# SCH_Ventilador_2025-02-20.net
KiCad netlist of a schematic drawn in EasyEDA
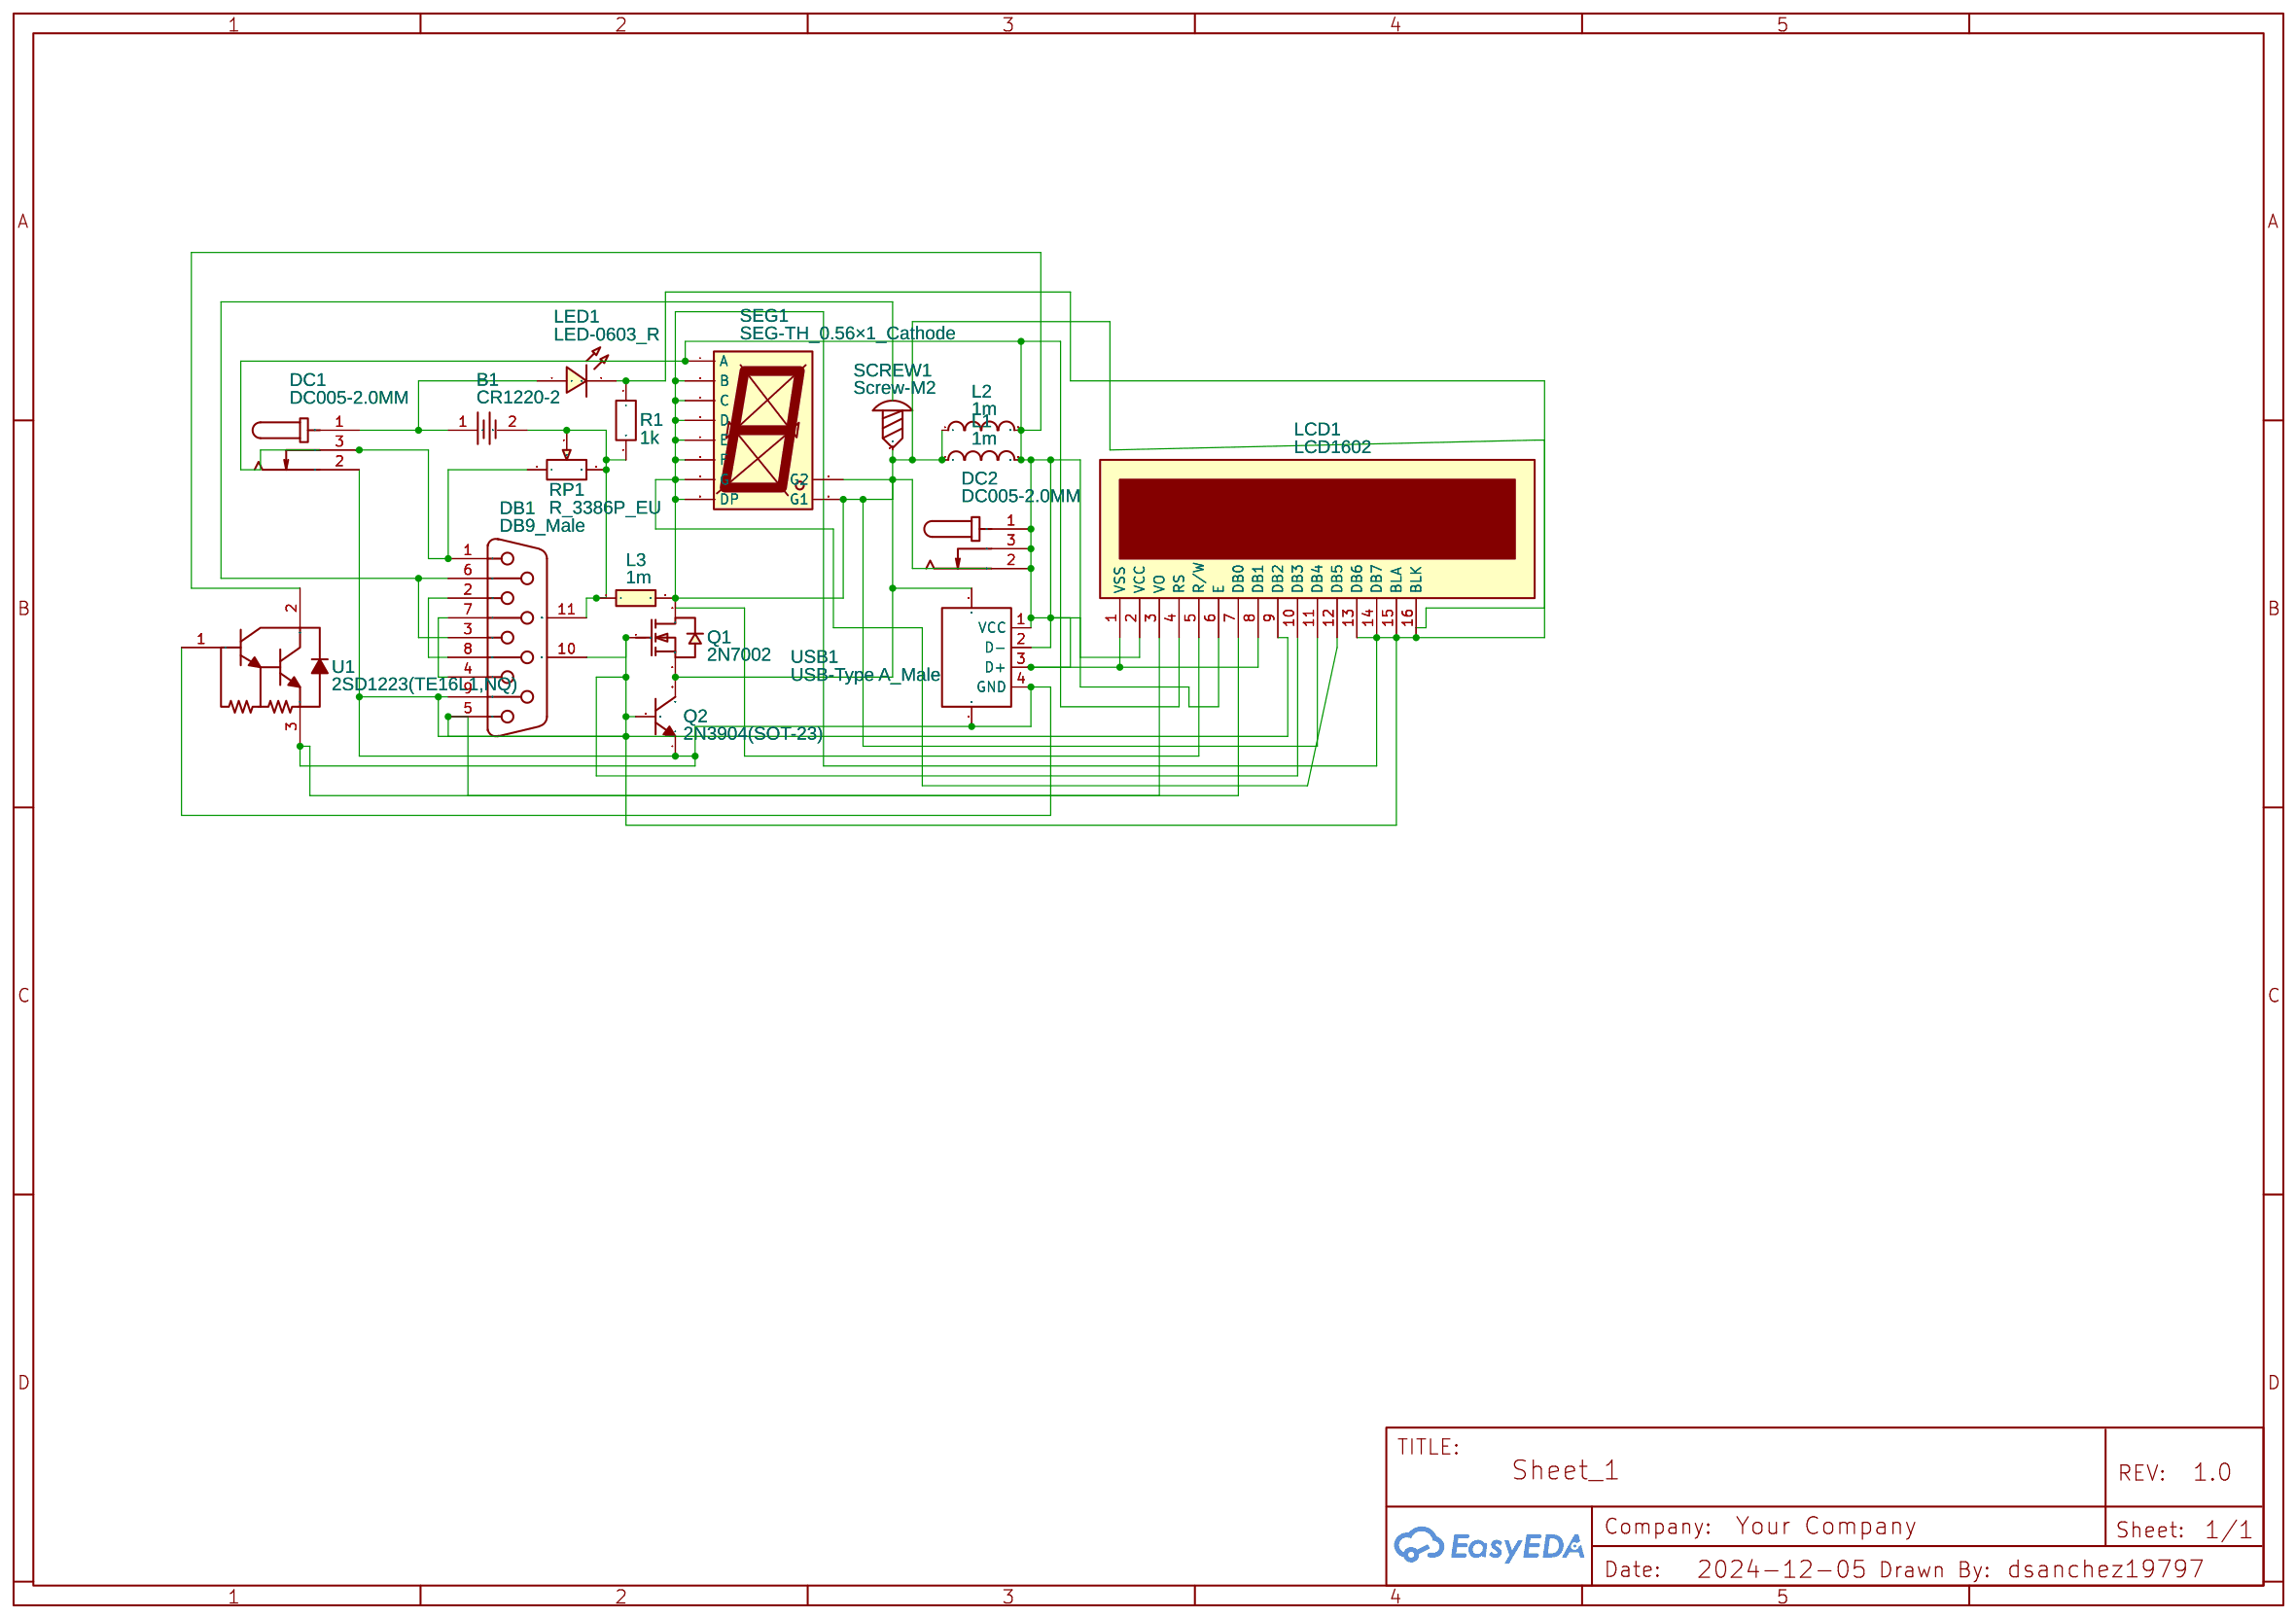
[diagram p0: schematic sheet]

(export (version "E")
  (design (tool "Eeschema 10.0.6"))
  (components
    (comp (ref "B1")
      (value "CR1220-2")
      (fields (field (name "Manufacturer") "Q&J"))
      (libsource (lib "") (part "CR1220-2"))
    )
    (comp (ref "DB1")
      (value "DB9_Male")
      (fields (field (name "Manufacturer") "Amphenol"))
      (libsource (lib "") (part "DB9_Male"))
    )
    (comp (ref "DC1")
      (value "DC005-2.0MM")
      (fields (field (name "Manufacturer") "SOFNG"))
      (libsource (lib "") (part "DC005-2.0MM"))
    )
    (comp (ref "DC2")
      (value "DC005-2.0MM")
      (fields (field (name "Manufacturer") "SOFNG"))
      (libsource (lib "") (part "DC005-2.0MM"))
    )
    (comp (ref "L1") (value "1m") (libsource (lib "") (part "L0603_US")))
    (comp (ref "L2") (value "1m") (libsource (lib "") (part "L0603_US")))
    (comp (ref "L3") (value "1m") (libsource (lib "") (part "L0603_EU")))
    (comp (ref "LCD1")
      (value "LCD1602")
      (fields
        (field (name "Manufacturer Part") "LCM1602K-NSW-BBW")
        (field (name "Manufacturer") "LONTECH(厦门龙特)")
      )
      (libsource (lib "") (part "LCD1602"))
    )
    (comp (ref "LED1")
      (value "LED-0603_R")
      (fields
        (field (name "Manufacturer Part") "19-217/R6C-AL1M2VY/3T")
        (field (name "Manufacturer") "EVERLIGHT(台湾亿光)")
      )
      (libsource (lib "") (part "LED-0603_R"))
    )
    (comp (ref "Q1")
      (value "2N7002")
      (fields (field (name "Manufacturer Part") "2N7002,215") (field (name "Manufacturer") "Nexperia"))
      (libsource (lib "") (part "2N7002"))
    )
    (comp (ref "Q2")
      (value "2N3904(SOT-23)")
      (fields (field (name "Manufacturer Part") "2n3904S-RTK/PS") (field (name "Manufacturer") "KEC"))
      (libsource (lib "") (part "2N3904(SOT-23)"))
    )
    (comp (ref "R1") (value "1k") (libsource (lib "") (part "R_0603_EU")))
    (comp (ref "RP1") (value "R_3386P_EU") (libsource (lib "") (part "R_3386P_EU")))
    (comp (ref "SCREW1") (value "Screw-M2") (libsource (lib "") (part "Screw-M2")))
    (comp (ref "SEG1")
      (value "SEG-TH_0.56×1_Cathode")
      (fields (field (name "Manufacturer") "志浩"))
      (libsource (lib "") (part "SEG-TH_0.56×1_Cathode"))
    )
    (comp (ref "U1")
      (value "2SD1223(TE16L1,NQ)")
      (fields (field (name "Manufacturer") "TOSHIBA(东芝)"))
      (libsource (lib "") (part "2SD1223(TE16L1,NQ)"))
    )
    (comp (ref "USB1")
      (value "USB-Type A_Male")
      (fields (field (name "Manufacturer Part") "USB-05") (field (name "Manufacturer") "SOFNG"))
      (libsource (lib "") (part "USB-Type A_Male"))
    )
  )
  (nets
    (net (code "1") (name "Net-(B1-Pad1)") (class "Default")
      (node (ref "B1") (pin "1") (pinfunction "1_1") (pintype "input"))
      (node (ref "DC1") (pin "1") (pinfunction "1_1") (pintype "unspecified"))
      (node (ref "LED1") (pin "1") (pinfunction "1_1") (pintype "unspecified"))
    )
    (net (code "2") (name "Net-(DB1-MH1)") (class "Default")
      (node (ref "DB1") (pin "1") (pinfunction "1_1") (pintype "input"))
      (node (ref "DB1") (pin "10") (pinfunction "MH1_10") (pintype "input"))
      (node (ref "DB1") (pin "5") (pinfunction "5_5") (pintype "input"))
      (node (ref "DB1") (pin "9") (pinfunction "9_9") (pintype "input"))
      (node (ref "DC1") (pin "2") (pinfunction "2_2") (pintype "unspecified"))
      (node (ref "DC1") (pin "3") (pinfunction "3_3") (pintype "unspecified"))
      (node (ref "DC2") (pin "1") (pinfunction "1_1") (pintype "unspecified"))
      (node (ref "DC2") (pin "2") (pinfunction "2_2") (pintype "unspecified"))
      (node (ref "DC2") (pin "3") (pinfunction "3_3") (pintype "unspecified"))
      (node (ref "L1") (pin "1") (pinfunction "1_1") (pintype "unspecified"))
      (node (ref "L1") (pin "2") (pinfunction "2_2") (pintype "unspecified"))
      (node (ref "L2") (pin "1") (pinfunction "1_1") (pintype "unspecified"))
      (node (ref "L2") (pin "2") (pinfunction "2_2") (pintype "unspecified"))
      (node (ref "L3") (pin "2") (pinfunction "2_2") (pintype "unspecified"))
      (node (ref "LCD1") (pin "1") (pinfunction "VSS_1") (pintype "unspecified"))
      (node (ref "LCD1") (pin "10") (pinfunction "DB3_10") (pintype "unspecified"))
      (node (ref "LCD1") (pin "11") (pinfunction "DB4_11") (pintype "unspecified"))
      (node (ref "LCD1") (pin "12") (pinfunction "DB5_12") (pintype "unspecified"))
      (node (ref "LCD1") (pin "13") (pinfunction "DB6_13") (pintype "unspecified"))
      (node (ref "LCD1") (pin "14") (pinfunction "DB7_14") (pintype "unspecified"))
      (node (ref "LCD1") (pin "15") (pinfunction "BLA_15") (pintype "unspecified"))
      (node (ref "LCD1") (pin "16") (pinfunction "BLK_16") (pintype "unspecified"))
      (node (ref "LCD1") (pin "2") (pinfunction "VCC_2") (pintype "unspecified"))
      (node (ref "LCD1") (pin "3") (pinfunction "VO_3") (pintype "unspecified"))
      (node (ref "LCD1") (pin "4") (pinfunction "RS_4") (pintype "unspecified"))
      (node (ref "LCD1") (pin "5") (pinfunction "R/W_5") (pintype "unspecified"))
      (node (ref "LCD1") (pin "6") (pinfunction "E_6") (pintype "unspecified"))
      (node (ref "LCD1") (pin "7") (pinfunction "DB0_7") (pintype "unspecified"))
      (node (ref "LCD1") (pin "8") (pinfunction "DB1_8") (pintype "unspecified"))
      (node (ref "LCD1") (pin "9") (pinfunction "DB2_9") (pintype "unspecified"))
      (node (ref "LED1") (pin "2") (pinfunction "2_2") (pintype "unspecified"))
      (node (ref "Q1") (pin "1") (pinfunction "G_1") (pintype "unspecified"))
      (node (ref "Q1") (pin "2") (pinfunction "S_2") (pintype "unspecified"))
      (node (ref "Q1") (pin "3") (pinfunction "D_3") (pintype "unspecified"))
      (node (ref "Q2") (pin "1") (pinfunction "E_1") (pintype "input"))
      (node (ref "Q2") (pin "2") (pinfunction "B_2") (pintype "input"))
      (node (ref "Q2") (pin "3") (pinfunction "C_3") (pintype "input"))
      (node (ref "R1") (pin "1") (pinfunction "1_1") (pintype "unspecified"))
      (node (ref "RP1") (pin "1") (pinfunction "1_1") (pintype "input"))
      (node (ref "SCREW1") (pin "1") (pinfunction "1_1") (pintype "unspecified"))
      (node (ref "SEG1") (pin "1") (pinfunction "E_1") (pintype "unspecified"))
      (node (ref "SEG1") (pin "10") (pinfunction "G_10") (pintype "unspecified"))
      (node (ref "SEG1") (pin "2") (pinfunction "D_2") (pintype "unspecified"))
      (node (ref "SEG1") (pin "3") (pinfunction "G1_3") (pintype "unspecified"))
      (node (ref "SEG1") (pin "4") (pinfunction "C_4") (pintype "unspecified"))
      (node (ref "SEG1") (pin "5") (pinfunction "DP_5") (pintype "unspecified"))
      (node (ref "SEG1") (pin "6") (pinfunction "B_6") (pintype "unspecified"))
      (node (ref "SEG1") (pin "7") (pinfunction "A_7") (pintype "unspecified"))
      (node (ref "SEG1") (pin "8") (pinfunction "G2_8") (pintype "unspecified"))
      (node (ref "SEG1") (pin "9") (pinfunction "F_9") (pintype "unspecified"))
      (node (ref "U1") (pin "1") (pinfunction "B_1") (pintype "unspecified"))
      (node (ref "U1") (pin "2") (pinfunction "C_2") (pintype "unspecified"))
      (node (ref "U1") (pin "3") (pinfunction "E_3") (pintype "unspecified"))
      (node (ref "USB1") (pin "1") (pinfunction "VCC_1") (pintype "input"))
      (node (ref "USB1") (pin "2") (pinfunction "D-_2") (pintype "input"))
      (node (ref "USB1") (pin "3") (pinfunction "D+_3") (pintype "input"))
      (node (ref "USB1") (pin "4") (pinfunction "GND_4") (pintype "input"))
      (node (ref "USB1") (pin "5") (pinfunction "5_5") (pintype "unspecified"))
      (node (ref "USB1") (pin "6") (pinfunction "6_6") (pintype "unspecified"))
    )
    (net (code "3") (name "Net-(DB1-MH2)") (class "Default")
      (node (ref "B1") (pin "2") (pinfunction "2_2") (pintype "input"))
      (node (ref "DB1") (pin "11") (pinfunction "MH2_11") (pintype "input"))
      (node (ref "L3") (pin "1") (pinfunction "1_1") (pintype "unspecified"))
      (node (ref "R1") (pin "2") (pinfunction "2_2") (pintype "unspecified"))
      (node (ref "RP1") (pin "2") (pinfunction "2_2") (pintype "input"))
      (node (ref "RP1") (pin "3") (pinfunction "3_3") (pintype "input"))
    )
    (net (code "4") (name "Net-(DB1-Pad2)") (class "Default")
      (node (ref "DB1") (pin "2") (pinfunction "2_2") (pintype "input"))
      (node (ref "DB1") (pin "8") (pinfunction "8_8") (pintype "input"))
    )
    (net (code "5") (name "Net-(DB1-Pad3)") (class "Default")
      (node (ref "DB1") (pin "3") (pinfunction "3_3") (pintype "input"))
      (node (ref "DB1") (pin "6") (pinfunction "6_6") (pintype "input"))
    )
    (net (code "6") (name "Net-(DB1-Pad4)") (class "Default")
      (node (ref "DB1") (pin "4") (pinfunction "4_4") (pintype "input"))
      (node (ref "DB1") (pin "7") (pinfunction "7_7") (pintype "input"))
    )
  )
)
